# DAUGHTER_POWER.net
KiCad netlist of a schematic drawn in EAGLE
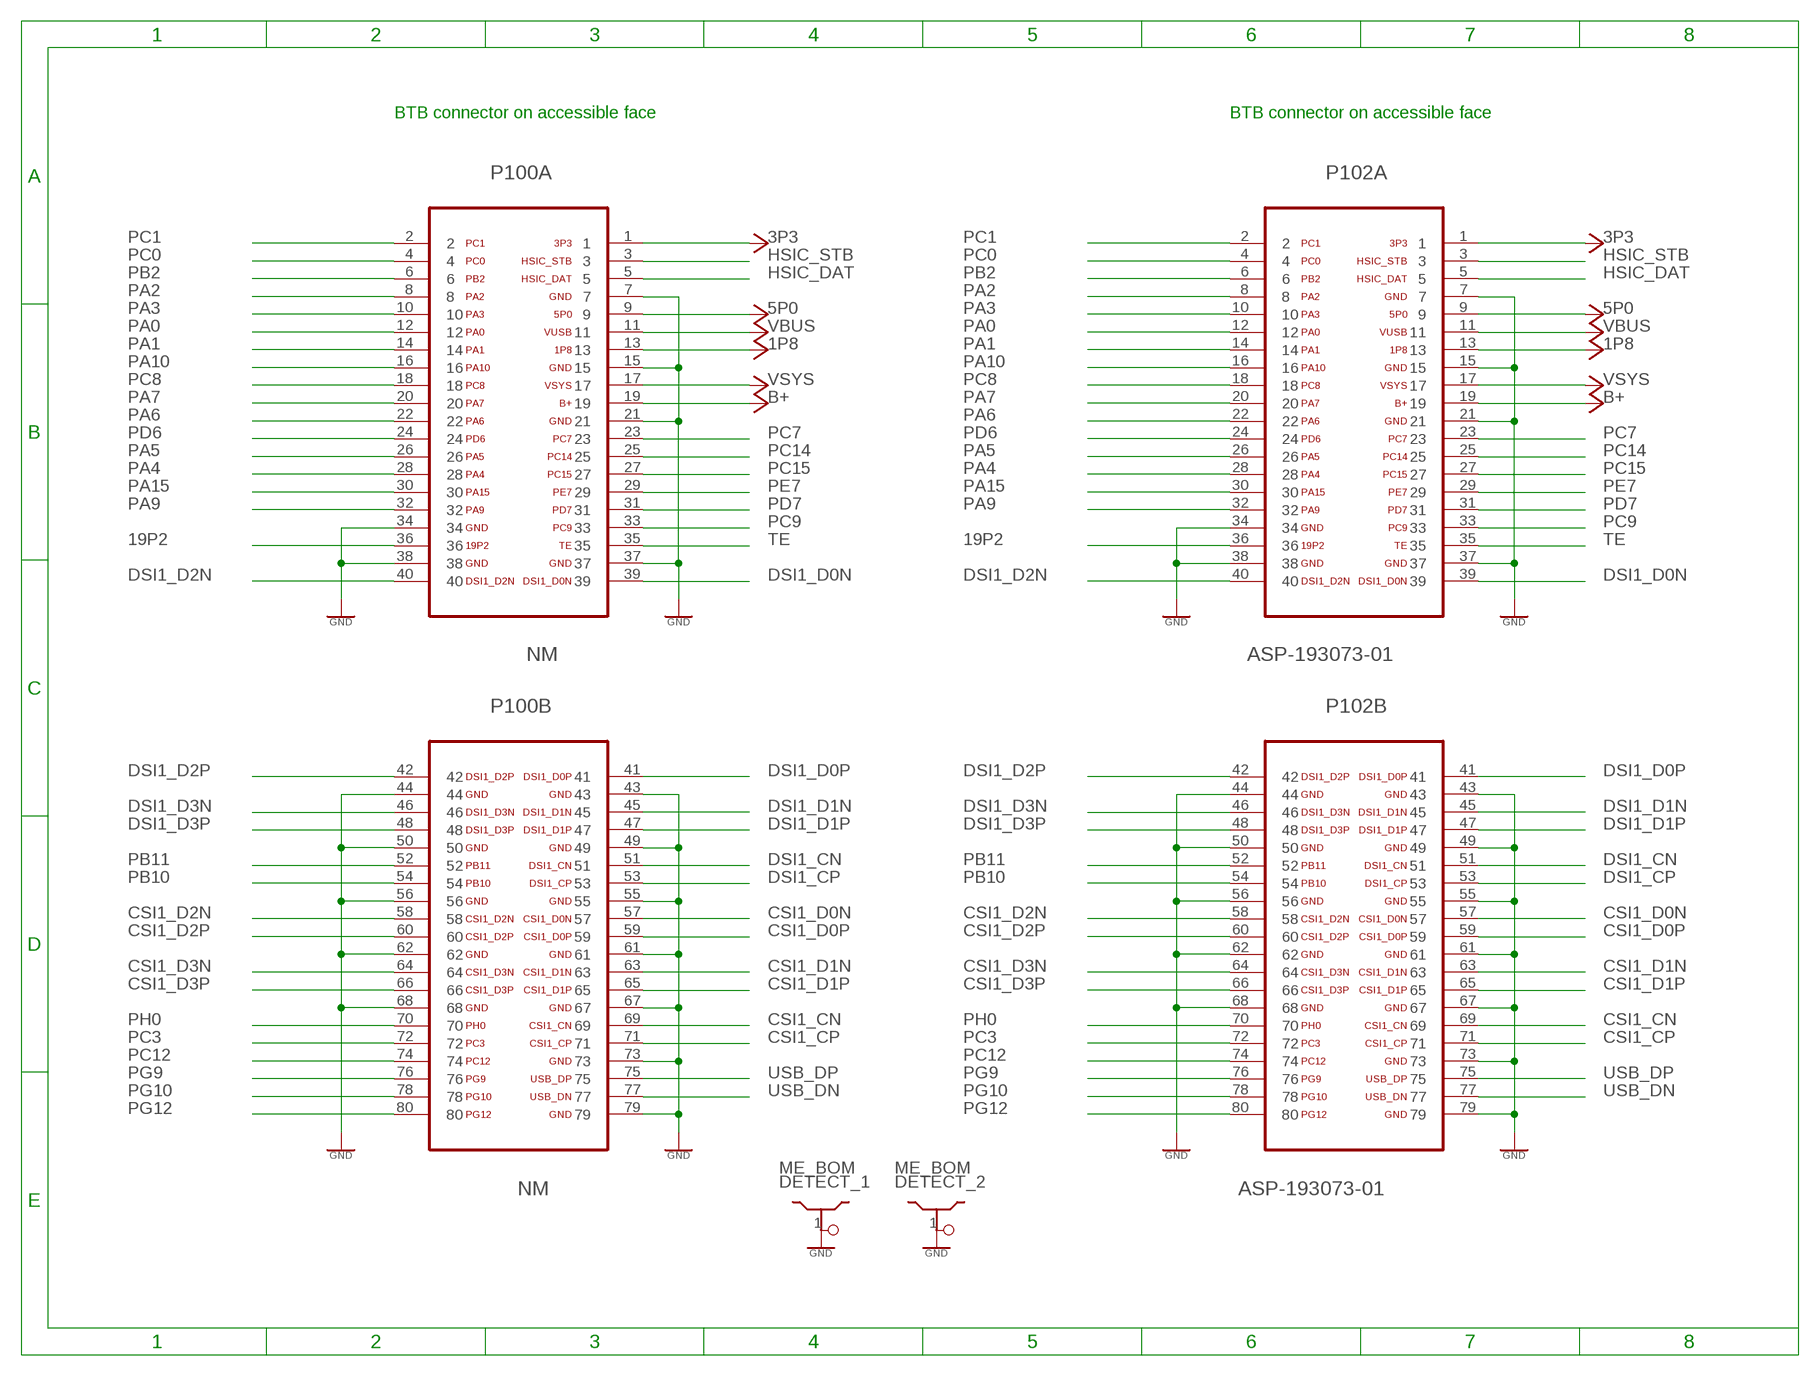
[diagram p0: schematic, sheet 1]
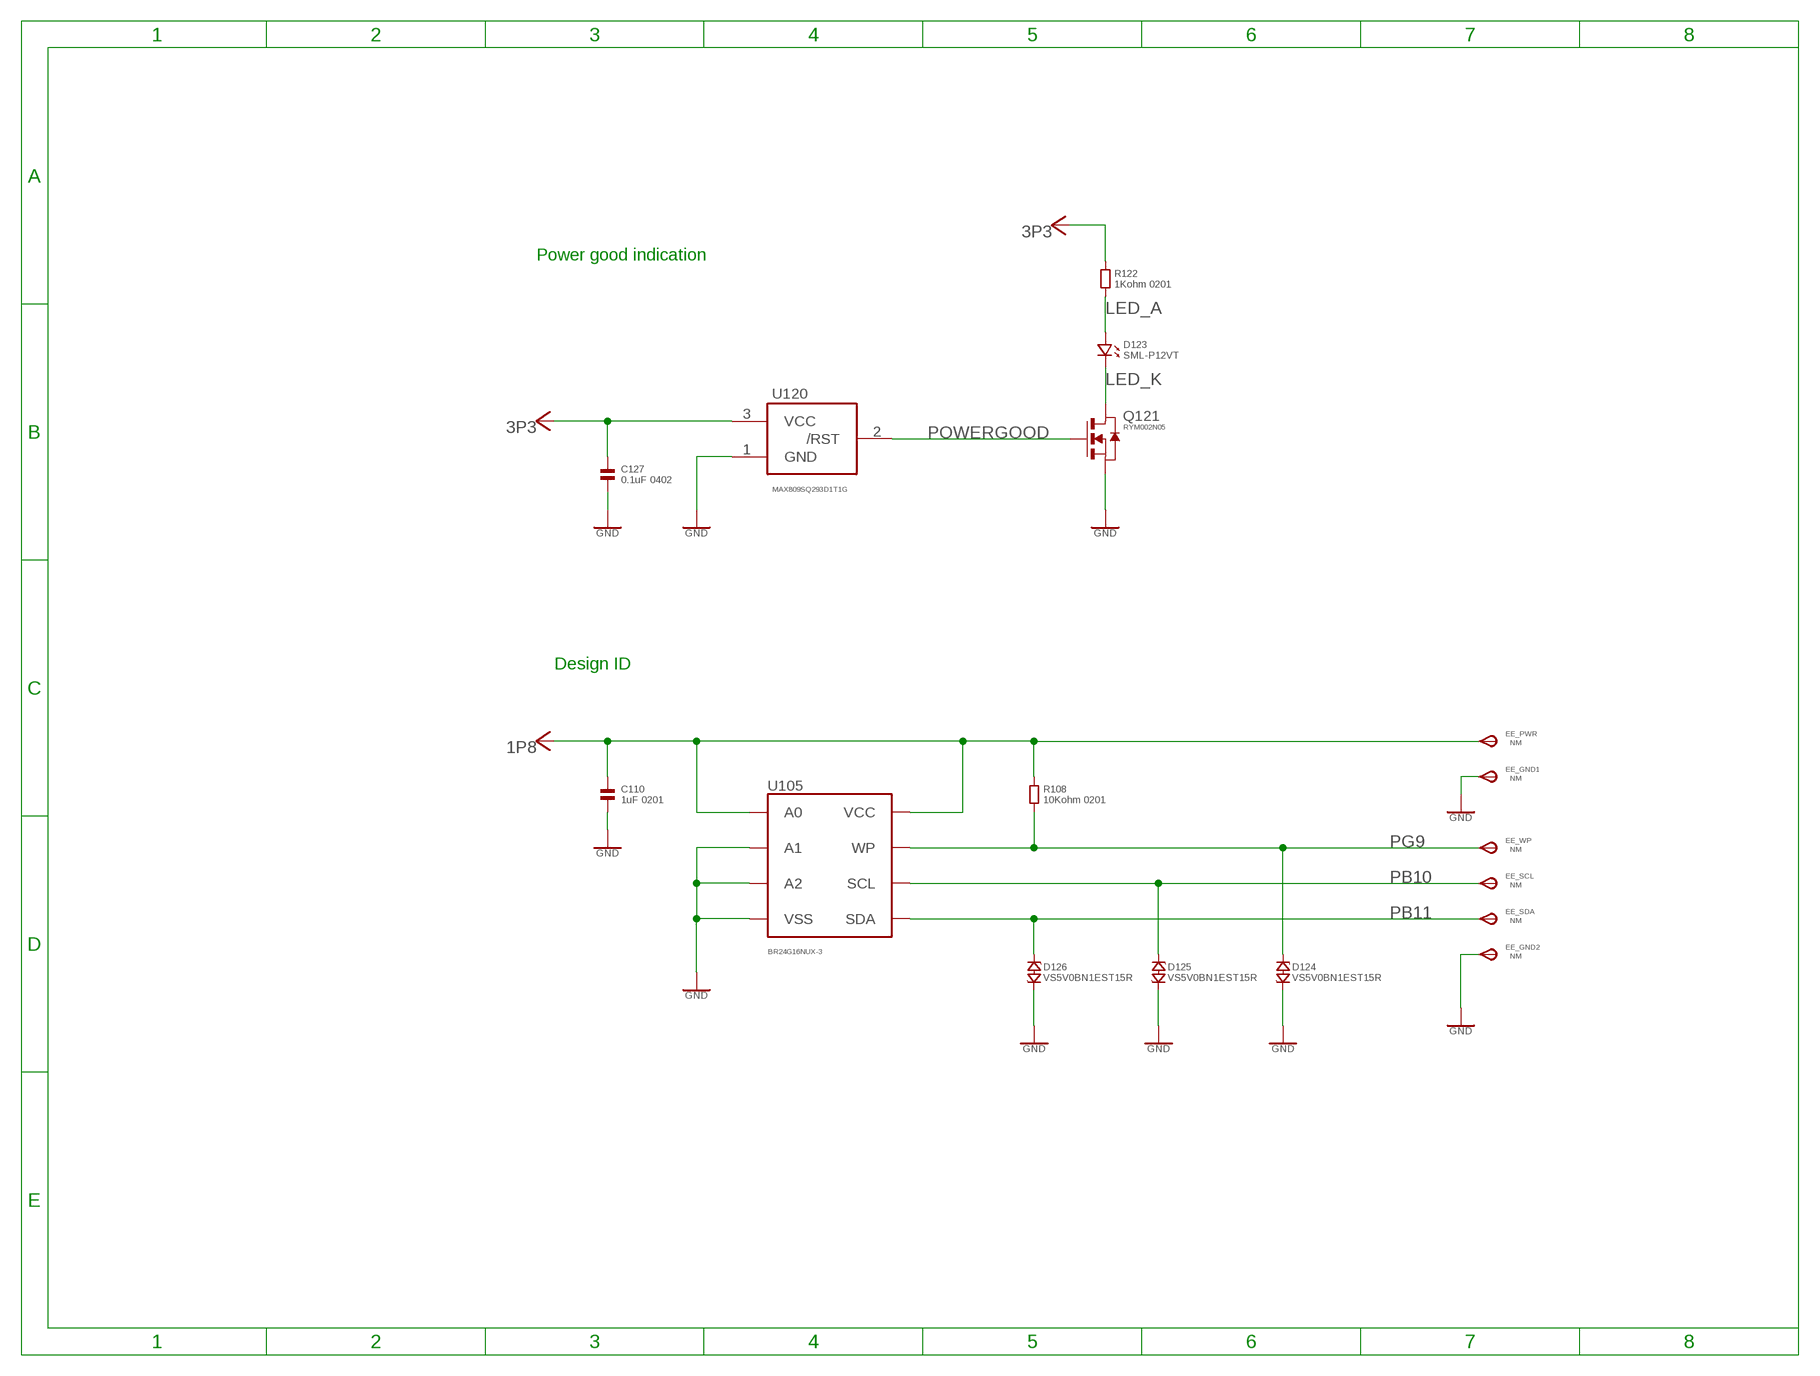
[diagram p1: schematic, sheet 2]
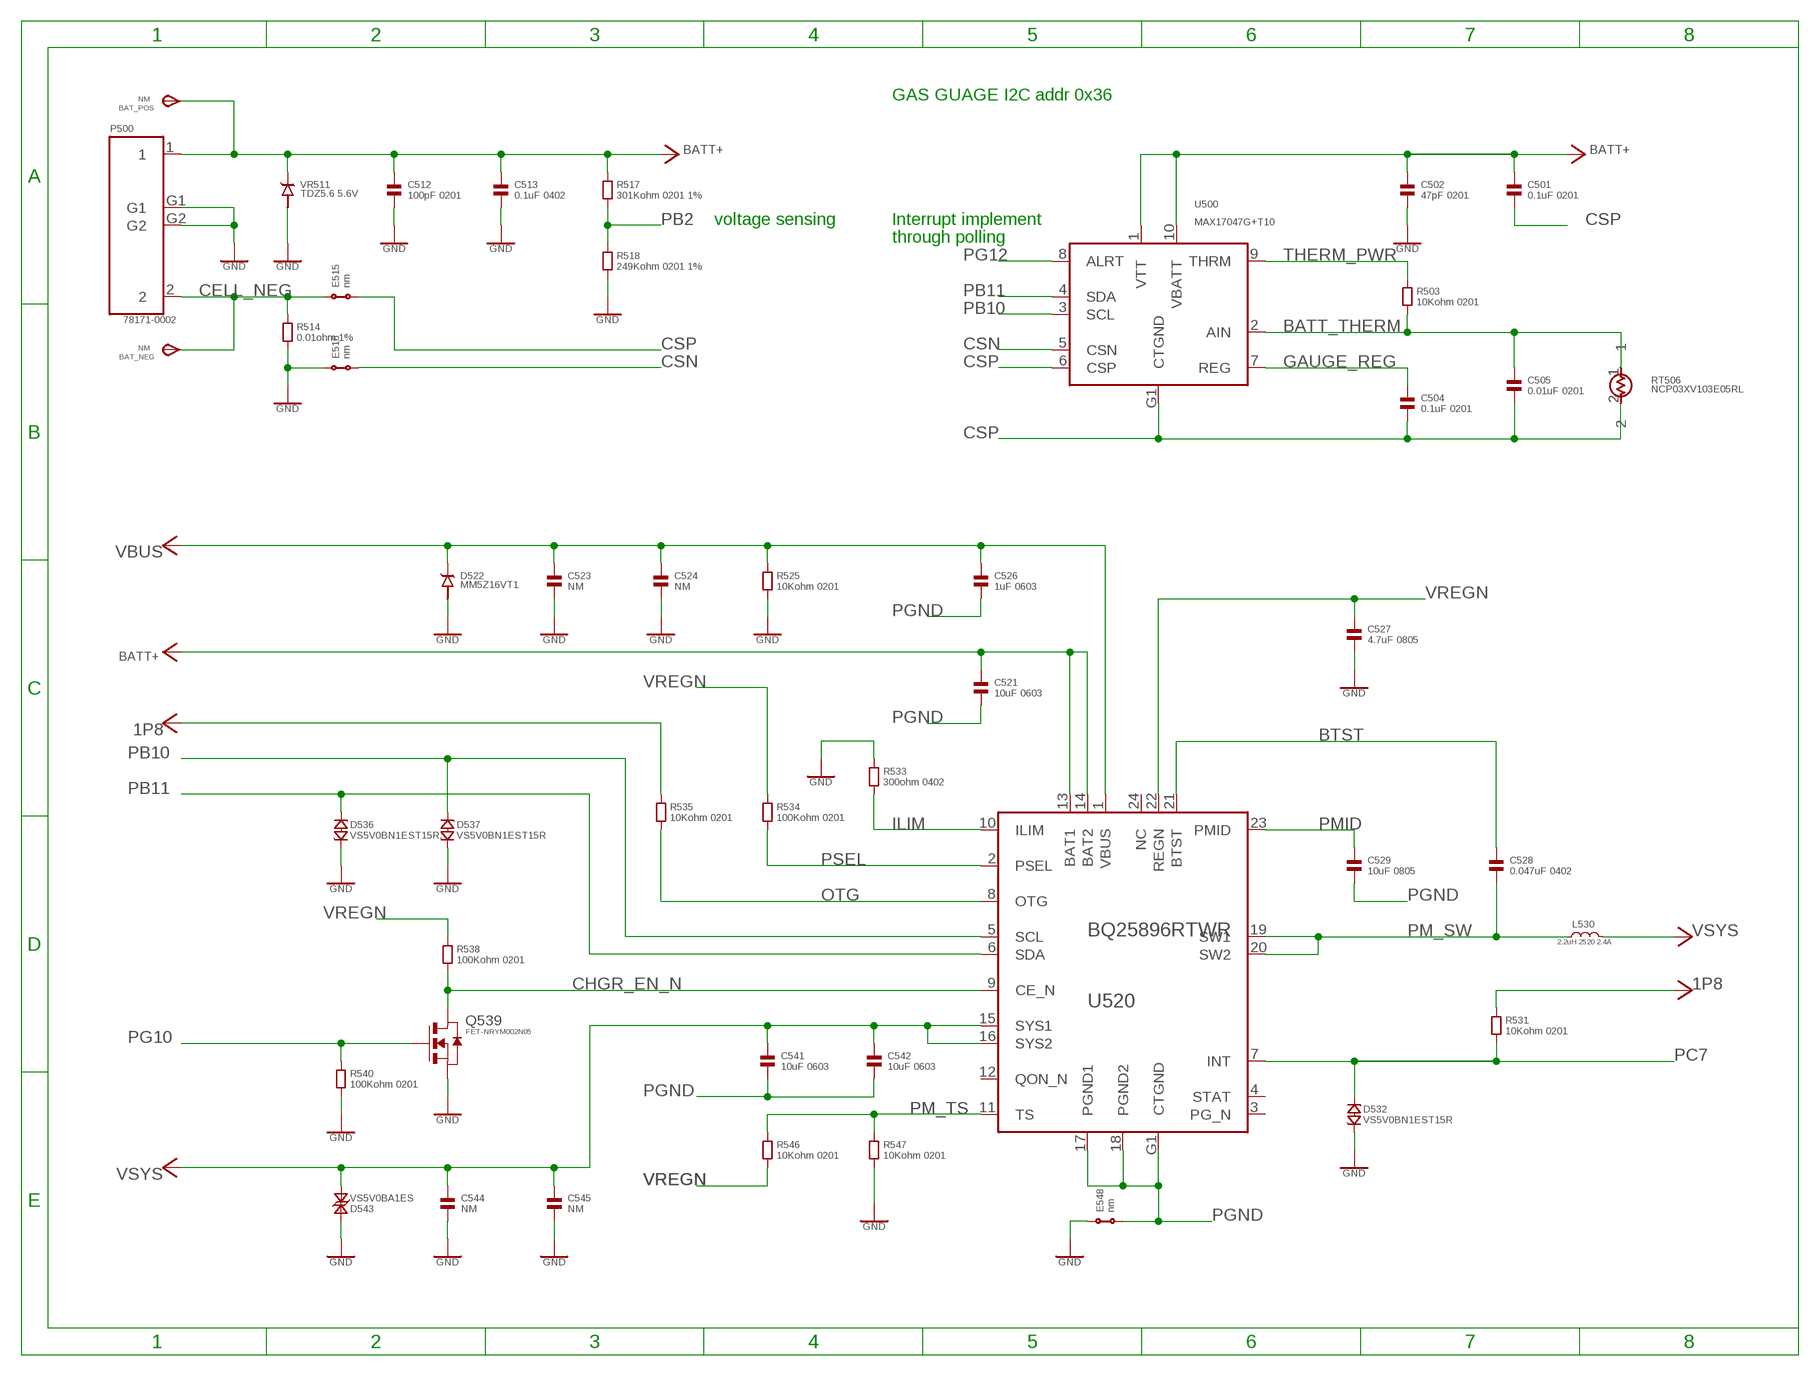
[diagram p2: schematic, sheet 3]

(export (version "E")
  (design (tool "Eeschema 10.0.6"))
  (components
    (comp (ref "BAT_NEG")
      (value "NM")
      (footprint "eagle-import:TP11R")
      (libsource (lib "eagle-import") (part "TPSTP11R"))
    )
    (comp (ref "BAT_POS")
      (value "NM")
      (footprint "eagle-import:TP11R")
      (libsource (lib "eagle-import") (part "TPSTP11R"))
    )
    (comp (ref "C501")
      (value "0.1uF 0201")
      (footprint "eagle-import:0201")
      (libsource (lib "eagle-import") (part "CAPACITOR.0201"))
    )
    (comp (ref "C502")
      (value "47pF 0201")
      (footprint "eagle-import:0201")
      (libsource (lib "eagle-import") (part "CAPACITOR.0201"))
    )
    (comp (ref "C504")
      (value "0.1uF 0201")
      (footprint "eagle-import:0201")
      (libsource (lib "eagle-import") (part "CAPACITOR.0201"))
    )
    (comp (ref "C505")
      (value "0.01uF 0201")
      (footprint "eagle-import:0201")
      (libsource (lib "eagle-import") (part "CAPACITOR.0201"))
    )
    (comp (ref "C512")
      (value "100pF 0201")
      (footprint "eagle-import:0201")
      (libsource (lib "eagle-import") (part "CAPACITOR.0201"))
    )
    (comp (ref "C513")
      (value "0.1uF 0402")
      (footprint "eagle-import:0402")
      (libsource (lib "eagle-import") (part "CAPACITOR.0402"))
    )
    (comp (ref "C521")
      (value "10uF 0603")
      (footprint "eagle-import:0603")
      (libsource (lib "eagle-import") (part "CAPACITOR.0603"))
    )
    (comp (ref "C523")
      (value "NM")
      (footprint "eagle-import:0201")
      (libsource (lib "eagle-import") (part "CAPACITOR.0201"))
    )
    (comp (ref "C524")
      (value "NM")
      (footprint "eagle-import:0201")
      (libsource (lib "eagle-import") (part "CAPACITOR.0201"))
    )
    (comp (ref "C526")
      (value "1uF 0603")
      (footprint "eagle-import:0603")
      (libsource (lib "eagle-import") (part "CAPACITOR.0603"))
    )
    (comp (ref "C527")
      (value "4.7uF 0805")
      (footprint "eagle-import:0805")
      (libsource (lib "eagle-import") (part "CAPACITOR.0805"))
    )
    (comp (ref "C528")
      (value "0.047uF 0402")
      (footprint "eagle-import:0402")
      (libsource (lib "eagle-import") (part "CAPACITOR.0402"))
    )
    (comp (ref "C529")
      (value "10uF 0805")
      (footprint "eagle-import:0805")
      (libsource (lib "eagle-import") (part "CAPACITOR.0805"))
    )
    (comp (ref "C541")
      (value "10uF 0603")
      (footprint "eagle-import:0603")
      (libsource (lib "eagle-import") (part "CAPACITOR.0603"))
    )
    (comp (ref "C542")
      (value "10uF 0603")
      (footprint "eagle-import:0603")
      (libsource (lib "eagle-import") (part "CAPACITOR.0603"))
    )
    (comp (ref "C544")
      (value "NM")
      (footprint "eagle-import:0201")
      (libsource (lib "eagle-import") (part "CAPACITOR.0201"))
    )
    (comp (ref "C545")
      (value "NM")
      (footprint "eagle-import:0201")
      (libsource (lib "eagle-import") (part "CAPACITOR.0201"))
    )
    (comp (ref "D522")
      (value "MM5Z16VT1")
      (footprint "eagle-import:SOD523")
      (libsource (lib "eagle-import") (part "DIODE.SOD523"))
    )
    (comp (ref "D532")
      (value "VS5V0BN1EST15R")
      (footprint "eagle-import:CHIP_0201")
      (libsource (lib "eagle-import") (part "ESD_VARISTOR.0201"))
    )
    (comp (ref "D536")
      (value "VS5V0BN1EST15R")
      (footprint "eagle-import:CHIP_0201")
      (libsource (lib "eagle-import") (part "ESD_VARISTOR.0201"))
    )
    (comp (ref "D537")
      (value "VS5V0BN1EST15R")
      (footprint "eagle-import:CHIP_0201")
      (libsource (lib "eagle-import") (part "ESD_VARISTOR.0201"))
    )
    (comp (ref "D543")
      (value "VS5V0BA1ES")
      (footprint "eagle-import:CHIP_0201")
      (fields (field (name "MPN") "UCLAMP1211Z"))
      (libsource (lib "eagle-import") (part "ESD_TVS.0201"))
    )
    (comp (ref "E515")
      (value "nm")
      (footprint "eagle-import:SHORT_DOT")
      (libsource (lib "eagle-import") (part "SHORT_DOT"))
    )
    (comp (ref "E516")
      (value "nm")
      (footprint "eagle-import:SHORT_DOT")
      (libsource (lib "eagle-import") (part "SHORT_DOT"))
    )
    (comp (ref "E548")
      (value "nm")
      (footprint "eagle-import:1X4_SHORT")
      (libsource (lib "eagle-import") (part "SHORT_BAR"))
    )
    (comp (ref "L530")
      (value "2.2uH 2520 2.4A")
      (footprint "eagle-import:2520")
      (libsource (lib "eagle-import") (part "POWER-INDUCTOR"))
    )
    (comp (ref "P500")
      (value "78171-0002")
      (footprint "eagle-import:CONN_4PIN")
      (libsource (lib "eagle-import") (part "CONN_BATT"))
    )
    (comp (ref "Q539")
      (value "FET-NRYM002N05")
      (footprint "eagle-import:VMT3")
      (fields (field (name "MPN") "RYM002N05"))
      (libsource (lib "eagle-import") (part "FET-NRYM002N05"))
    )
    (comp (ref "R503")
      (value "10Kohm 0201")
      (footprint "eagle-import:0201")
      (libsource (lib "eagle-import") (part "RESISTOR.0201"))
    )
    (comp (ref "R514")
      (value "0.01ohm 1%")
      (footprint "eagle-import:0805")
      (libsource (lib "eagle-import") (part "RESISTOR.0805"))
    )
    (comp (ref "R517")
      (value "301Kohm 0201 1%")
      (footprint "eagle-import:0201")
      (libsource (lib "eagle-import") (part "RESISTOR.0201"))
    )
    (comp (ref "R518")
      (value "249Kohm 0201 1%")
      (footprint "eagle-import:0201")
      (libsource (lib "eagle-import") (part "RESISTOR.0201"))
    )
    (comp (ref "R525")
      (value "10Kohm 0201")
      (footprint "eagle-import:0201")
      (libsource (lib "eagle-import") (part "RESISTOR.0201"))
    )
    (comp (ref "R531")
      (value "10Kohm 0201")
      (footprint "eagle-import:0201")
      (libsource (lib "eagle-import") (part "RESISTOR.0201"))
    )
    (comp (ref "R533")
      (value "300ohm 0402")
      (footprint "eagle-import:0402")
      (libsource (lib "eagle-import") (part "RESISTOR.0402"))
    )
    (comp (ref "R534")
      (value "100Kohm 0201")
      (footprint "eagle-import:0201")
      (libsource (lib "eagle-import") (part "RESISTOR.0201"))
    )
    (comp (ref "R535")
      (value "10Kohm 0201")
      (footprint "eagle-import:0201")
      (libsource (lib "eagle-import") (part "RESISTOR.0201"))
    )
    (comp (ref "R538")
      (value "100Kohm 0201")
      (footprint "eagle-import:0201")
      (libsource (lib "eagle-import") (part "RESISTOR.0201"))
    )
    (comp (ref "R540")
      (value "100Kohm 0201")
      (footprint "eagle-import:0201")
      (libsource (lib "eagle-import") (part "RESISTOR.0201"))
    )
    (comp (ref "R546")
      (value "10Kohm 0201")
      (footprint "eagle-import:0201")
      (libsource (lib "eagle-import") (part "RESISTOR.0201"))
    )
    (comp (ref "R547")
      (value "10Kohm 0201")
      (footprint "eagle-import:0201")
      (libsource (lib "eagle-import") (part "RESISTOR.0201"))
    )
    (comp (ref "RT506")
      (value "NCP03XV103E05RL")
      (footprint "eagle-import:0201")
      (fields (field (name "MPN") "NCP03XV103XV103E05RL/NTCG0603UH103HT"))
      (libsource (lib "eagle-import") (part "THERMISTOR"))
    )
    (comp (ref "U500")
      (value "MAX17047G+T10")
      (footprint "eagle-import:DFN3X3_PS0_5P11")
      (libsource (lib "eagle-import") (part "MAX17047G+T10"))
    )
    (comp (ref "U520")
      (value "BQ25896RTWR")
      (footprint "eagle-import:QFN4X4PS0_5P25")
      (libsource (lib "eagle-import") (part "BQ25896RTWR"))
    )
    (comp (ref "VR511")
      (value "TDZ5.6 5.6V")
      (footprint "eagle-import:DIO1_9X1_3")
      (fields (field (name "MPN") "TDZ5.6B"))
      (libsource (lib "eagle-import") (part "DIODE"))
    )
    (comp (ref "C110")
      (value "1uF 0201")
      (footprint "eagle-import:0201")
      (libsource (lib "eagle-import") (part "CAPACITOR.0201"))
    )
    (comp (ref "C127")
      (value "0.1uF 0402")
      (footprint "eagle-import:0402")
      (libsource (lib "eagle-import") (part "CAPACITOR.0402"))
    )
    (comp (ref "D123")
      (value "SML-P12VT")
      (footprint "eagle-import:0503.LED")
      (libsource (lib "eagle-import") (part "LED.0503"))
    )
    (comp (ref "D124")
      (value "VS5V0BN1EST15R")
      (footprint "eagle-import:CHIP_0201")
      (libsource (lib "eagle-import") (part "ESD_VARISTOR.0201"))
    )
    (comp (ref "D125")
      (value "VS5V0BN1EST15R")
      (footprint "eagle-import:CHIP_0201")
      (libsource (lib "eagle-import") (part "ESD_VARISTOR.0201"))
    )
    (comp (ref "D126")
      (value "VS5V0BN1EST15R")
      (footprint "eagle-import:CHIP_0201")
      (libsource (lib "eagle-import") (part "ESD_VARISTOR.0201"))
    )
    (comp (ref "EE_GND1")
      (value "NM")
      (footprint "eagle-import:TP11R")
      (libsource (lib "eagle-import") (part "TPSTP11R"))
    )
    (comp (ref "EE_GND2")
      (value "NM")
      (footprint "eagle-import:TP11R")
      (libsource (lib "eagle-import") (part "TPSTP11R"))
    )
    (comp (ref "EE_PWR")
      (value "NM")
      (footprint "eagle-import:TP11R")
      (libsource (lib "eagle-import") (part "TPSTP11R"))
    )
    (comp (ref "EE_SCL")
      (value "NM")
      (footprint "eagle-import:TP11R")
      (libsource (lib "eagle-import") (part "TPSTP11R"))
    )
    (comp (ref "EE_SDA")
      (value "NM")
      (footprint "eagle-import:TP11R")
      (libsource (lib "eagle-import") (part "TPSTP11R"))
    )
    (comp (ref "EE_WP")
      (value "NM")
      (footprint "eagle-import:TP11R")
      (libsource (lib "eagle-import") (part "TPSTP11R"))
    )
    (comp (ref "Q121")
      (value "RYM002N05")
      (footprint "eagle-import:VMT3")
      (libsource (lib "eagle-import") (part "FET-NRYM002N05"))
    )
    (comp (ref "R108")
      (value "10Kohm 0201")
      (footprint "eagle-import:0201")
      (libsource (lib "eagle-import") (part "RESISTOR.0201"))
    )
    (comp (ref "R122")
      (value "1Kohm 0201")
      (footprint "eagle-import:0201")
      (libsource (lib "eagle-import") (part "RESISTOR.0201"))
    )
    (comp (ref "U105")
      (value "BR24G16NUX-3")
      (footprint "eagle-import:DFN-8")
      (libsource (lib "eagle-import") (part "EEPROMDFN8"))
    )
    (comp (ref "U120")
      (value "MAX809SQ293D1T1G")
      (footprint "eagle-import:SC70-3L")
      (fields (field (name "MPN") "MAX809SQ293D1T1"))
      (libsource (lib "eagle-import") (part "MAX809"))
    )
    (comp (ref "DETECT_1")
      (value "ME_BOM")
      (footprint "eagle-import:PLUG")
      (fields (field (name "MPN") "refer to ME BOM"))
      (libsource (lib "eagle-import") (part "SHIELDDETECT"))
    )
    (comp (ref "DETECT_2")
      (value "ME_BOM")
      (footprint "eagle-import:PLUG")
      (fields (field (name "MPN") "refer to ME BOM"))
      (libsource (lib "eagle-import") (part "SHIELDDETECT"))
    )
    (comp (ref "P100")
      (value "NM")
      (footprint "eagle-import:CLM-140-02-L-D-K_GOLD")
      (fields (field (name "MPN") "CLM-140-02-L-D-K"))
      (libsource (lib "eagle-import") (part "CLM-140-02-L-D-KGOLD"))
    )
    (comp (ref "P102")
      (value "ASP-193073-01")
      (footprint "eagle-import:FTMH-140-02-L-DV-ES-P-TR")
      (fields (field (name "MPN") "ASP-193073-01"))
      (libsource (lib "eagle-import") (part "FTMH-140-02-L-DV-ES-P-TR"))
    )
  )
  (nets
    (net (code "1") (name "1P8") (class "Default")
      (node (ref "C110") (pin "1") (pinfunction "1_1") (pintype "bidirectional"))
      (node (ref "EE_PWR") (pin "TP") (pinfunction "PP_TP") (pintype "input"))
      (node (ref "P100") (pin "13") (pinfunction "13_13") (pintype "passive"))
      (node (ref "P102") (pin "13") (pinfunction "13_13") (pintype "passive"))
      (node (ref "R108") (pin "1") (pinfunction "1_1") (pintype "bidirectional"))
      (node (ref "R531") (pin "1") (pinfunction "1_1") (pintype "bidirectional"))
      (node (ref "R535") (pin "1") (pinfunction "1_1") (pintype "bidirectional"))
      (node (ref "U105") (pin "P$1") (pinfunction "A0_P$1") (pintype "input"))
      (node (ref "U105") (pin "P$8") (pinfunction "VCC_P$8") (pintype "power_in"))
    )
    (net (code "2") (name "3P3") (class "Default")
      (node (ref "C127") (pin "1") (pinfunction "1_1") (pintype "bidirectional"))
      (node (ref "P100") (pin "1") (pinfunction "1_1") (pintype "passive"))
      (node (ref "P102") (pin "1") (pinfunction "1_1") (pintype "passive"))
      (node (ref "R122") (pin "1") (pinfunction "1_1") (pintype "bidirectional"))
      (node (ref "U120") (pin "3") (pinfunction "VCC_3") (pintype "input"))
    )
    (net (code "3") (name "5P0") (class "Default")
      (node (ref "P100") (pin "9") (pinfunction "9_9") (pintype "passive"))
      (node (ref "P102") (pin "9") (pinfunction "9_9") (pintype "passive"))
    )
    (net (code "4") (name "19P2") (class "Default")
      (node (ref "P100") (pin "36") (pinfunction "36_36") (pintype "passive"))
      (node (ref "P102") (pin "36") (pinfunction "36_36") (pintype "passive"))
    )
    (net (code "5") (name "B+") (class "Default")
      (node (ref "P100") (pin "19") (pinfunction "19_19") (pintype "passive"))
      (node (ref "P102") (pin "19") (pinfunction "19_19") (pintype "passive"))
    )
    (net (code "6") (name "BATT+") (class "Default")
      (node (ref "BAT_POS") (pin "TP") (pinfunction "PP_TP") (pintype "input"))
      (node (ref "C501") (pin "1") (pinfunction "1_1") (pintype "bidirectional"))
      (node (ref "C502") (pin "1") (pinfunction "1_1") (pintype "bidirectional"))
      (node (ref "C512") (pin "1") (pinfunction "1_1") (pintype "bidirectional"))
      (node (ref "C513") (pin "1") (pinfunction "1_1") (pintype "bidirectional"))
      (node (ref "C521") (pin "1") (pinfunction "1_1") (pintype "bidirectional"))
      (node (ref "P500") (pin "1") (pinfunction "1_1") (pintype "bidirectional"))
      (node (ref "R517") (pin "1") (pinfunction "1_1") (pintype "bidirectional"))
      (node (ref "U500") (pin "1") (pinfunction "VTT_1") (pintype "bidirectional"))
      (node (ref "U500") (pin "10") (pinfunction "VBATT_10") (pintype "bidirectional"))
      (node (ref "U520") (pin "13") (pinfunction "BAT1_13") (pintype "bidirectional"))
      (node (ref "U520") (pin "14") (pinfunction "BAT2_14") (pintype "bidirectional"))
      (node (ref "VR511") (pin "1") (pinfunction "1_1") (pintype "bidirectional"))
    )
    (net (code "7") (name "BATT_THERM") (class "Default")
      (node (ref "C505") (pin "1") (pinfunction "1_1") (pintype "bidirectional"))
      (node (ref "R503") (pin "2") (pinfunction "2_2") (pintype "bidirectional"))
      (node (ref "RT506") (pin "1") (pinfunction "1_1") (pintype "bidirectional"))
      (node (ref "U500") (pin "2") (pinfunction "AIN_2") (pintype "bidirectional"))
    )
    (net (code "8") (name "BTST") (class "Default")
      (node (ref "C528") (pin "1") (pinfunction "1_1") (pintype "bidirectional"))
      (node (ref "U520") (pin "21") (pinfunction "BTST_21") (pintype "bidirectional"))
    )
    (net (code "9") (name "CELL_NEG") (class "Default")
      (node (ref "BAT_NEG") (pin "TP") (pinfunction "PP_TP") (pintype "input"))
      (node (ref "E515") (pin "1") (pinfunction "1_1") (pintype "bidirectional"))
      (node (ref "P500") (pin "2") (pinfunction "2_2") (pintype "bidirectional"))
      (node (ref "R514") (pin "1") (pinfunction "1_1") (pintype "bidirectional"))
    )
    (net (code "10") (name "CHGR_EN_N") (class "Default")
      (node (ref "Q539") (pin "3") (pinfunction "D_3") (pintype "passive"))
      (node (ref "R538") (pin "2") (pinfunction "2_2") (pintype "bidirectional"))
      (node (ref "U520") (pin "9") (pinfunction "CE_N_9") (pintype "bidirectional"))
    )
    (net (code "11") (name "CSI1_CN") (class "Default")
      (node (ref "P100") (pin "69") (pinfunction "69_69") (pintype "passive"))
      (node (ref "P102") (pin "69") (pinfunction "69_69") (pintype "passive"))
    )
    (net (code "12") (name "CSI1_CP") (class "Default")
      (node (ref "P100") (pin "71") (pinfunction "71_71") (pintype "passive"))
      (node (ref "P102") (pin "71") (pinfunction "71_71") (pintype "passive"))
    )
    (net (code "13") (name "CSI1_D0N") (class "Default")
      (node (ref "P100") (pin "57") (pinfunction "57_57") (pintype "passive"))
      (node (ref "P102") (pin "57") (pinfunction "57_57") (pintype "passive"))
    )
    (net (code "14") (name "CSI1_D0P") (class "Default")
      (node (ref "P100") (pin "59") (pinfunction "59_59") (pintype "passive"))
      (node (ref "P102") (pin "59") (pinfunction "59_59") (pintype "passive"))
    )
    (net (code "15") (name "CSI1_D1N") (class "Default")
      (node (ref "P100") (pin "63") (pinfunction "63_63") (pintype "passive"))
      (node (ref "P102") (pin "63") (pinfunction "63_63") (pintype "passive"))
    )
    (net (code "16") (name "CSI1_D1P") (class "Default")
      (node (ref "P100") (pin "65") (pinfunction "65_65") (pintype "passive"))
      (node (ref "P102") (pin "65") (pinfunction "65_65") (pintype "passive"))
    )
    (net (code "17") (name "CSI1_D2N") (class "Default")
      (node (ref "P100") (pin "58") (pinfunction "58_58") (pintype "passive"))
      (node (ref "P102") (pin "58") (pinfunction "58_58") (pintype "passive"))
    )
    (net (code "18") (name "CSI1_D2P") (class "Default")
      (node (ref "P100") (pin "60") (pinfunction "60_60") (pintype "passive"))
      (node (ref "P102") (pin "60") (pinfunction "60_60") (pintype "passive"))
    )
    (net (code "19") (name "CSI1_D3N") (class "Default")
      (node (ref "P100") (pin "64") (pinfunction "64_64") (pintype "passive"))
      (node (ref "P102") (pin "64") (pinfunction "64_64") (pintype "passive"))
    )
    (net (code "20") (name "CSI1_D3P") (class "Default")
      (node (ref "P100") (pin "66") (pinfunction "66_66") (pintype "passive"))
      (node (ref "P102") (pin "66") (pinfunction "66_66") (pintype "passive"))
    )
    (net (code "21") (name "CSN") (class "Default")
      (node (ref "E516") (pin "2") (pinfunction "2_2") (pintype "bidirectional"))
      (node (ref "U500") (pin "5") (pinfunction "CSN_5") (pintype "bidirectional"))
    )
    (net (code "22") (name "CSP") (class "Default")
      (node (ref "C501") (pin "2") (pinfunction "2_2") (pintype "bidirectional"))
      (node (ref "C504") (pin "2") (pinfunction "2_2") (pintype "bidirectional"))
      (node (ref "C505") (pin "2") (pinfunction "2_2") (pintype "bidirectional"))
      (node (ref "E515") (pin "2") (pinfunction "2_2") (pintype "bidirectional"))
      (node (ref "RT506") (pin "2") (pinfunction "2_2") (pintype "bidirectional"))
      (node (ref "U500") (pin "6") (pinfunction "CSP_6") (pintype "bidirectional"))
      (node (ref "U500") (pin "G1") (pinfunction "CTGND_G1") (pintype "bidirectional"))
    )
    (net (code "23") (name "DSI1_CN") (class "Default")
      (node (ref "P100") (pin "51") (pinfunction "51_51") (pintype "passive"))
      (node (ref "P102") (pin "51") (pinfunction "51_51") (pintype "passive"))
    )
    (net (code "24") (name "DSI1_CP") (class "Default")
      (node (ref "P100") (pin "53") (pinfunction "53_53") (pintype "passive"))
      (node (ref "P102") (pin "53") (pinfunction "53_53") (pintype "passive"))
    )
    (net (code "25") (name "DSI1_D0N") (class "Default")
      (node (ref "P100") (pin "39") (pinfunction "39_39") (pintype "passive"))
      (node (ref "P102") (pin "39") (pinfunction "39_39") (pintype "passive"))
    )
    (net (code "26") (name "DSI1_D0P") (class "Default")
      (node (ref "P100") (pin "41") (pinfunction "41_41") (pintype "passive"))
      (node (ref "P102") (pin "41") (pinfunction "41_41") (pintype "passive"))
    )
    (net (code "27") (name "DSI1_D1N") (class "Default")
      (node (ref "P100") (pin "45") (pinfunction "45_45") (pintype "passive"))
      (node (ref "P102") (pin "45") (pinfunction "45_45") (pintype "passive"))
    )
    (net (code "28") (name "DSI1_D1P") (class "Default")
      (node (ref "P100") (pin "47") (pinfunction "47_47") (pintype "passive"))
      (node (ref "P102") (pin "47") (pinfunction "47_47") (pintype "passive"))
    )
    (net (code "29") (name "DSI1_D2N") (class "Default")
      (node (ref "P100") (pin "40") (pinfunction "40_40") (pintype "passive"))
      (node (ref "P102") (pin "40") (pinfunction "40_40") (pintype "passive"))
    )
    (net (code "30") (name "DSI1_D2P") (class "Default")
      (node (ref "P100") (pin "42") (pinfunction "42_42") (pintype "passive"))
      (node (ref "P102") (pin "42") (pinfunction "42_42") (pintype "passive"))
    )
    (net (code "31") (name "DSI1_D3N") (class "Default")
      (node (ref "P100") (pin "46") (pinfunction "46_46") (pintype "passive"))
      (node (ref "P102") (pin "46") (pinfunction "46_46") (pintype "passive"))
    )
    (net (code "32") (name "DSI1_D3P") (class "Default")
      (node (ref "P100") (pin "48") (pinfunction "48_48") (pintype "passive"))
      (node (ref "P102") (pin "48") (pinfunction "48_48") (pintype "passive"))
    )
    (net (code "33") (name "GAUGE_REG") (class "Default")
      (node (ref "C504") (pin "1") (pinfunction "1_1") (pintype "bidirectional"))
      (node (ref "U500") (pin "7") (pinfunction "REG_7") (pintype "bidirectional"))
    )
    (net (code "34") (name "GND") (class "Default")
      (node (ref "C110") (pin "2") (pinfunction "2_2") (pintype "bidirectional"))
      (node (ref "C127") (pin "2") (pinfunction "2_2") (pintype "bidirectional"))
      (node (ref "C502") (pin "2") (pinfunction "2_2") (pintype "bidirectional"))
      (node (ref "C512") (pin "2") (pinfunction "2_2") (pintype "bidirectional"))
      (node (ref "C513") (pin "2") (pinfunction "2_2") (pintype "bidirectional"))
      (node (ref "C523") (pin "2") (pinfunction "2_2") (pintype "bidirectional"))
      (node (ref "C524") (pin "2") (pinfunction "2_2") (pintype "bidirectional"))
      (node (ref "C527") (pin "2") (pinfunction "2_2") (pintype "bidirectional"))
      (node (ref "C544") (pin "2") (pinfunction "2_2") (pintype "bidirectional"))
      (node (ref "C545") (pin "2") (pinfunction "2_2") (pintype "bidirectional"))
      (node (ref "D124") (pin "P$2") (pinfunction "2_P$2") (pintype "bidirectional"))
      (node (ref "D125") (pin "P$2") (pinfunction "2_P$2") (pintype "bidirectional"))
      (node (ref "D126") (pin "P$2") (pinfunction "2_P$2") (pintype "bidirectional"))
      (node (ref "D522") (pin "2") (pinfunction "2_2") (pintype "bidirectional"))
      (node (ref "D532") (pin "P$2") (pinfunction "2_P$2") (pintype "bidirectional"))
      (node (ref "D536") (pin "P$2") (pinfunction "2_P$2") (pintype "bidirectional"))
      (node (ref "D537") (pin "P$2") (pinfunction "2_P$2") (pintype "bidirectional"))
      (node (ref "D543") (pin "P$1") (pinfunction "1_P$1") (pintype "bidirectional"))
      (node (ref "DETECT_1") (pin "1") (pinfunction "1_1") (pintype "passive"))
      (node (ref "DETECT_2") (pin "1") (pinfunction "1_1") (pintype "passive"))
      (node (ref "E516") (pin "1") (pinfunction "1_1") (pintype "bidirectional"))
      (node (ref "E548") (pin "1") (pinfunction "1_1") (pintype "bidirectional"))
      (node (ref "EE_GND1") (pin "TP") (pinfunction "PP_TP") (pintype "input"))
      (node (ref "EE_GND2") (pin "TP") (pinfunction "PP_TP") (pintype "input"))
      (node (ref "P100") (pin "15") (pinfunction "15_15") (pintype "passive"))
      (node (ref "P100") (pin "21") (pinfunction "21_21") (pintype "passive"))
      (node (ref "P100") (pin "34") (pinfunction "34_34") (pintype "passive"))
      (node (ref "P100") (pin "37") (pinfunction "37_37") (pintype "passive"))
      (node (ref "P100") (pin "38") (pinfunction "38_38") (pintype "passive"))
      (node (ref "P100") (pin "43") (pinfunction "43_43") (pintype "passive"))
      (node (ref "P100") (pin "44") (pinfunction "44_44") (pintype "passive"))
      (node (ref "P100") (pin "49") (pinfunction "49_49") (pintype "passive"))
      (node (ref "P100") (pin "50") (pinfunction "50_50") (pintype "passive"))
      (node (ref "P100") (pin "55") (pinfunction "55_55") (pintype "passive"))
      (node (ref "P100") (pin "56") (pinfunction "56_56") (pintype "passive"))
      (node (ref "P100") (pin "61") (pinfunction "61_61") (pintype "passive"))
      (node (ref "P100") (pin "62") (pinfunction "62_62") (pintype "passive"))
      (node (ref "P100") (pin "67") (pinfunction "67_67") (pintype "passive"))
      (node (ref "P100") (pin "68") (pinfunction "68_68") (pintype "passive"))
      (node (ref "P100") (pin "7") (pinfunction "7_7") (pintype "passive"))
      (node (ref "P100") (pin "73") (pinfunction "73_73") (pintype "passive"))
      (node (ref "P100") (pin "79") (pinfunction "79_79") (pintype "passive"))
      (node (ref "P102") (pin "15") (pinfunction "15_15") (pintype "passive"))
      (node (ref "P102") (pin "21") (pinfunction "21_21") (pintype "passive"))
      (node (ref "P102") (pin "34") (pinfunction "34_34") (pintype "passive"))
      (node (ref "P102") (pin "37") (pinfunction "37_37") (pintype "passive"))
      (node (ref "P102") (pin "38") (pinfunction "38_38") (pintype "passive"))
      (node (ref "P102") (pin "43") (pinfunction "43_43") (pintype "passive"))
      (node (ref "P102") (pin "44") (pinfunction "44_44") (pintype "passive"))
      (node (ref "P102") (pin "49") (pinfunction "49_49") (pintype "passive"))
      (node (ref "P102") (pin "50") (pinfunction "50_50") (pintype "passive"))
      (node (ref "P102") (pin "55") (pinfunction "55_55") (pintype "passive"))
      (node (ref "P102") (pin "56") (pinfunction "56_56") (pintype "passive"))
      (node (ref "P102") (pin "61") (pinfunction "61_61") (pintype "passive"))
      (node (ref "P102") (pin "62") (pinfunction "62_62") (pintype "passive"))
      (node (ref "P102") (pin "67") (pinfunction "67_67") (pintype "passive"))
      (node (ref "P102") (pin "68") (pinfunction "68_68") (pintype "passive"))
      (node (ref "P102") (pin "7") (pinfunction "7_7") (pintype "passive"))
      (node (ref "P102") (pin "73") (pinfunction "73_73") (pintype "passive"))
      (node (ref "P102") (pin "79") (pinfunction "79_79") (pintype "passive"))
      (node (ref "P500") (pin "G1") (pinfunction "G1_G1") (pintype "bidirectional"))
      (node (ref "P500") (pin "G2") (pinfunction "G2_G2") (pintype "bidirectional"))
      (node (ref "Q121") (pin "2") (pinfunction "S_2") (pintype "passive"))
      (node (ref "Q539") (pin "2") (pinfunction "S_2") (pintype "passive"))
      (node (ref "R514") (pin "2") (pinfunction "2_2") (pintype "bidirectional"))
      (node (ref "R518") (pin "2") (pinfunction "2_2") (pintype "bidirectional"))
      (node (ref "R525") (pin "2") (pinfunction "2_2") (pintype "bidirectional"))
      (node (ref "R533") (pin "1") (pinfunction "1_1") (pintype "bidirectional"))
      (node (ref "R540") (pin "2") (pinfunction "2_2") (pintype "bidirectional"))
      (node (ref "R547") (pin "2") (pinfunction "2_2") (pintype "bidirectional"))
      (node (ref "U105") (pin "P$2") (pinfunction "A1_P$2") (pintype "input"))
      (node (ref "U105") (pin "P$3") (pinfunction "A2_P$3") (pintype "input"))
      (node (ref "U105") (pin "P$4") (pinfunction "VSS_P$4") (pintype "power_in"))
      (node (ref "U105") (pin "P$9") (pinfunction "VSS_P$9") (pintype "power_in"))
      (node (ref "U120") (pin "1") (pinfunction "GND_1") (pintype "power_in"))
      (node (ref "VR511") (pin "2") (pinfunction "2_2") (pintype "bidirectional"))
    )
    (net (code "35") (name "HSIC_DAT") (class "Default")
      (node (ref "P100") (pin "5") (pinfunction "5_5") (pintype "passive"))
      (node (ref "P102") (pin "5") (pinfunction "5_5") (pintype "passive"))
    )
    (net (code "36") (name "HSIC_STB") (class "Default")
      (node (ref "P100") (pin "3") (pinfunction "3_3") (pintype "passive"))
      (node (ref "P102") (pin "3") (pinfunction "3_3") (pintype "passive"))
    )
    (net (code "37") (name "ILIM") (class "Default")
      (node (ref "R533") (pin "2") (pinfunction "2_2") (pintype "bidirectional"))
      (node (ref "U520") (pin "10") (pinfunction "ILIM_10") (pintype "bidirectional"))
    )
    (net (code "38") (name "LED_A") (class "Default")
      (node (ref "D123") (pin "P$1") (pinfunction "1_P$1") (pintype "bidirectional"))
      (node (ref "R122") (pin "2") (pinfunction "2_2") (pintype "bidirectional"))
    )
    (net (code "39") (name "LED_K") (class "Default")
      (node (ref "D123") (pin "P$2") (pinfunction "2_P$2") (pintype "bidirectional"))
      (node (ref "Q121") (pin "3") (pinfunction "D_3") (pintype "passive"))
    )
    (net (code "40") (name "OTG") (class "Default")
      (node (ref "R535") (pin "2") (pinfunction "2_2") (pintype "bidirectional"))
      (node (ref "U520") (pin "8") (pinfunction "OTG_8") (pintype "bidirectional"))
    )
    (net (code "41") (name "PA0") (class "Default")
      (node (ref "P100") (pin "12") (pinfunction "12_12") (pintype "passive"))
      (node (ref "P102") (pin "12") (pinfunction "12_12") (pintype "passive"))
    )
    (net (code "42") (name "PA1") (class "Default")
      (node (ref "P100") (pin "14") (pinfunction "14_14") (pintype "passive"))
      (node (ref "P102") (pin "14") (pinfunction "14_14") (pintype "passive"))
    )
    (net (code "43") (name "PA2") (class "Default")
      (node (ref "P100") (pin "8") (pinfunction "8_8") (pintype "passive"))
      (node (ref "P102") (pin "8") (pinfunction "8_8") (pintype "passive"))
    )
    (net (code "44") (name "PA3") (class "Default")
      (node (ref "P100") (pin "10") (pinfunction "10_10") (pintype "passive"))
      (node (ref "P102") (pin "10") (pinfunction "10_10") (pintype "passive"))
    )
    (net (code "45") (name "PA4") (class "Default")
      (node (ref "P100") (pin "28") (pinfunction "28_28") (pintype "passive"))
      (node (ref "P102") (pin "28") (pinfunction "28_28") (pintype "passive"))
    )
    (net (code "46") (name "PA5") (class "Default")
      (node (ref "P100") (pin "26") (pinfunction "26_26") (pintype "passive"))
      (node (ref "P102") (pin "26") (pinfunction "26_26") (pintype "passive"))
    )
    (net (code "47") (name "PA6") (class "Default")
      (node (ref "P100") (pin "22") (pinfunction "22_22") (pintype "passive"))
      (node (ref "P102") (pin "22") (pinfunction "22_22") (pintype "passive"))
    )
    (net (code "48") (name "PA7") (class "Default")
      (node (ref "P100") (pin "20") (pinfunction "20_20") (pintype "passive"))
      (node (ref "P102") (pin "20") (pinfunction "20_20") (pintype "passive"))
    )
    (net (code "49") (name "PA9") (class "Default")
      (node (ref "P100") (pin "32") (pinfunction "32_32") (pintype "passive"))
      (node (ref "P102") (pin "32") (pinfunction "32_32") (pintype "passive"))
    )
    (net (code "50") (name "PA10") (class "Default")
      (node (ref "P100") (pin "16") (pinfunction "16_16") (pintype "passive"))
      (node (ref "P102") (pin "16") (pinfunction "16_16") (pintype "passive"))
    )
    (net (code "51") (name "PA15") (class "Default")
      (node (ref "P100") (pin "30") (pinfunction "30_30") (pintype "passive"))
      (node (ref "P102") (pin "30") (pinfunction "30_30") (pintype "passive"))
    )
    (net (code "52") (name "PB2") (class "Default")
      (node (ref "P100") (pin "6") (pinfunction "6_6") (pintype "passive"))
      (node (ref "P102") (pin "6") (pinfunction "6_6") (pintype "passive"))
      (node (ref "R517") (pin "2") (pinfunction "2_2") (pintype "bidirectional"))
      (node (ref "R518") (pin "1") (pinfunction "1_1") (pintype "bidirectional"))
    )
    (net (code "53") (name "PB10") (class "Default")
      (node (ref "D125") (pin "P$1") (pinfunction "1_P$1") (pintype "bidirectional"))
      (node (ref "D537") (pin "P$1") (pinfunction "1_P$1") (pintype "bidirectional"))
      (node (ref "EE_SCL") (pin "TP") (pinfunction "PP_TP") (pintype "input"))
      (node (ref "P100") (pin "54") (pinfunction "54_54") (pintype "passive"))
      (node (ref "P102") (pin "54") (pinfunction "54_54") (pintype "passive"))
      (node (ref "U105") (pin "P$6") (pinfunction "SCL_P$6") (pintype "input"))
      (node (ref "U500") (pin "3") (pinfunction "SCL_3") (pintype "bidirectional"))
      (node (ref "U520") (pin "5") (pinfunction "SCL_5") (pintype "bidirectional"))
    )
    (net (code "54") (name "PB11") (class "Default")
      (node (ref "D126") (pin "P$1") (pinfunction "1_P$1") (pintype "bidirectional"))
      (node (ref "D536") (pin "P$1") (pinfunction "1_P$1") (pintype "bidirectional"))
      (node (ref "EE_SDA") (pin "TP") (pinfunction "PP_TP") (pintype "input"))
      (node (ref "P100") (pin "52") (pinfunction "52_52") (pintype "passive"))
      (node (ref "P102") (pin "52") (pinfunction "52_52") (pintype "passive"))
      (node (ref "U105") (pin "P$5") (pinfunction "SDA_P$5") (pintype "bidirectional"))
      (node (ref "U500") (pin "4") (pinfunction "SDA_4") (pintype "bidirectional"))
      (node (ref "U520") (pin "6") (pinfunction "SDA_6") (pintype "bidirectional"))
    )
    (net (code "55") (name "PC0") (class "Default")
      (node (ref "P100") (pin "4") (pinfunction "4_4") (pintype "passive"))
      (node (ref "P102") (pin "4") (pinfunction "4_4") (pintype "passive"))
    )
    (net (code "56") (name "PC1") (class "Default")
      (node (ref "P100") (pin "2") (pinfunction "2_2") (pintype "passive"))
      (node (ref "P102") (pin "2") (pinfunction "2_2") (pintype "passive"))
    )
    (net (code "57") (name "PC3") (class "Default")
      (node (ref "P100") (pin "72") (pinfunction "72_72") (pintype "passive"))
      (node (ref "P102") (pin "72") (pinfunction "72_72") (pintype "passive"))
    )
    (net (code "58") (name "PC7") (class "Default")
      (node (ref "D532") (pin "P$1") (pinfunction "1_P$1") (pintype "bidirectional"))
      (node (ref "P100") (pin "23") (pinfunction "23_23") (pintype "passive"))
      (node (ref "P102") (pin "23") (pinfunction "23_23") (pintype "passive"))
      (node (ref "R531") (pin "2") (pinfunction "2_2") (pintype "bidirectional"))
      (node (ref "U520") (pin "7") (pinfunction "INT_7") (pintype "bidirectional"))
    )
    (net (code "59") (name "PC8") (class "Default")
      (node (ref "P100") (pin "18") (pinfunction "18_18") (pintype "passive"))
      (node (ref "P102") (pin "18") (pinfunction "18_18") (pintype "passive"))
    )
    (net (code "60") (name "PC9") (class "Default")
      (node (ref "P100") (pin "33") (pinfunction "33_33") (pintype "passive"))
      (node (ref "P102") (pin "33") (pinfunction "33_33") (pintype "passive"))
    )
    (net (code "61") (name "PC12") (class "Default")
      (node (ref "P100") (pin "74") (pinfunction "74_74") (pintype "passive"))
      (node (ref "P102") (pin "74") (pinfunction "74_74") (pintype "passive"))
    )
    (net (code "62") (name "PC14") (class "Default")
      (node (ref "P100") (pin "25") (pinfunction "25_25") (pintype "passive"))
      (node (ref "P102") (pin "25") (pinfunction "25_25") (pintype "passive"))
    )
    (net (code "63") (name "PC15") (class "Default")
      (node (ref "P100") (pin "27") (pinfunction "27_27") (pintype "passive"))
      (node (ref "P102") (pin "27") (pinfunction "27_27") (pintype "passive"))
    )
    (net (code "64") (name "PD6") (class "Default")
      (node (ref "P100") (pin "24") (pinfunction "24_24") (pintype "passive"))
      (node (ref "P102") (pin "24") (pinfunction "24_24") (pintype "passive"))
    )
    (net (code "65") (name "PD7") (class "Default")
      (node (ref "P100") (pin "31") (pinfunction "31_31") (pintype "passive"))
      (node (ref "P102") (pin "31") (pinfunction "31_31") (pintype "passive"))
    )
    (net (code "66") (name "PE7") (class "Default")
      (node (ref "P100") (pin "29") (pinfunction "29_29") (pintype "passive"))
      (node (ref "P102") (pin "29") (pinfunction "29_29") (pintype "passive"))
    )
    (net (code "67") (name "PG9") (class "Default")
      (node (ref "D124") (pin "P$1") (pinfunction "1_P$1") (pintype "bidirectional"))
      (node (ref "EE_WP") (pin "TP") (pinfunction "PP_TP") (pintype "input"))
      (node (ref "P100") (pin "76") (pinfunction "76_76") (pintype "passive"))
      (node (ref "P102") (pin "76") (pinfunction "76_76") (pintype "passive"))
      (node (ref "R108") (pin "2") (pinfunction "2_2") (pintype "bidirectional"))
      (node (ref "U105") (pin "P$7") (pinfunction "WP_P$7") (pintype "input"))
    )
    (net (code "68") (name "PG10") (class "Default")
      (node (ref "P100") (pin "78") (pinfunction "78_78") (pintype "passive"))
      (node (ref "P102") (pin "78") (pinfunction "78_78") (pintype "passive"))
      (node (ref "Q539") (pin "1") (pinfunction "G_1") (pintype "passive"))
      (node (ref "R540") (pin "1") (pinfunction "1_1") (pintype "bidirectional"))
    )
    (net (code "69") (name "PG12") (class "Default")
      (node (ref "P100") (pin "80") (pinfunction "80_80") (pintype "passive"))
      (node (ref "P102") (pin "80") (pinfunction "80_80") (pintype "passive"))
      (node (ref "U500") (pin "8") (pinfunction "ALRT_8") (pintype "bidirectional"))
    )
    (net (code "70") (name "PGND") (class "Default")
      (node (ref "C521") (pin "2") (pinfunction "2_2") (pintype "bidirectional"))
      (node (ref "C526") (pin "2") (pinfunction "2_2") (pintype "bidirectional"))
      (node (ref "C529") (pin "2") (pinfunction "2_2") (pintype "bidirectional"))
      (node (ref "C541") (pin "2") (pinfunction "2_2") (pintype "bidirectional"))
      (node (ref "C542") (pin "2") (pinfunction "2_2") (pintype "bidirectional"))
      (node (ref "E548") (pin "2") (pinfunction "2_2") (pintype "bidirectional"))
      (node (ref "U520") (pin "17") (pinfunction "PGND1_17") (pintype "bidirectional"))
      (node (ref "U520") (pin "18") (pinfunction "PGND2_18") (pintype "bidirectional"))
      (node (ref "U520") (pin "G1") (pinfunction "CTGND_G1") (pintype "bidirectional"))
    )
    (net (code "71") (name "PH0") (class "Default")
      (node (ref "P100") (pin "70") (pinfunction "70_70") (pintype "passive"))
      (node (ref "P102") (pin "70") (pinfunction "70_70") (pintype "passive"))
    )
    (net (code "72") (name "PMID") (class "Default")
      (node (ref "C529") (pin "1") (pinfunction "1_1") (pintype "bidirectional"))
      (node (ref "U520") (pin "23") (pinfunction "PMID_23") (pintype "bidirectional"))
    )
    (net (code "73") (name "PM_SW") (class "Default")
      (node (ref "C528") (pin "2") (pinfunction "2_2") (pintype "bidirectional"))
      (node (ref "L530") (pin "G1") (pinfunction "1_G1") (pintype "passive"))
      (node (ref "U520") (pin "19") (pinfunction "SW1_19") (pintype "bidirectional"))
      (node (ref "U520") (pin "20") (pinfunction "SW2_20") (pintype "bidirectional"))
    )
    (net (code "74") (name "PM_TS") (class "Default")
      (node (ref "R546") (pin "1") (pinfunction "1_1") (pintype "bidirectional"))
      (node (ref "R547") (pin "1") (pinfunction "1_1") (pintype "bidirectional"))
      (node (ref "U520") (pin "11") (pinfunction "TS_11") (pintype "bidirectional"))
    )
    (net (code "75") (name "POWERGOOD") (class "Default")
      (node (ref "Q121") (pin "1") (pinfunction "G_1") (pintype "passive"))
      (node (ref "U120") (pin "2") (pinfunction "/RST_2") (pintype "output"))
    )
    (net (code "76") (name "PSEL") (class "Default")
      (node (ref "R534") (pin "2") (pinfunction "2_2") (pintype "bidirectional"))
      (node (ref "U520") (pin "2") (pinfunction "PSEL_2") (pintype "bidirectional"))
    )
    (net (code "77") (name "TE") (class "Default")
      (node (ref "P100") (pin "35") (pinfunction "35_35") (pintype "passive"))
      (node (ref "P102") (pin "35") (pinfunction "35_35") (pintype "passive"))
    )
    (net (code "78") (name "THERM_PWR") (class "Default")
      (node (ref "R503") (pin "1") (pinfunction "1_1") (pintype "bidirectional"))
      (node (ref "U500") (pin "9") (pinfunction "THRM_9") (pintype "bidirectional"))
    )
    (net (code "79") (name "USB_DN") (class "Default")
      (node (ref "P100") (pin "77") (pinfunction "77_77") (pintype "passive"))
      (node (ref "P102") (pin "77") (pinfunction "77_77") (pintype "passive"))
    )
    (net (code "80") (name "USB_DP") (class "Default")
      (node (ref "P100") (pin "75") (pinfunction "75_75") (pintype "passive"))
      (node (ref "P102") (pin "75") (pinfunction "75_75") (pintype "passive"))
    )
    (net (code "81") (name "VBUS") (class "Default")
      (node (ref "C523") (pin "1") (pinfunction "1_1") (pintype "bidirectional"))
      (node (ref "C524") (pin "1") (pinfunction "1_1") (pintype "bidirectional"))
      (node (ref "C526") (pin "1") (pinfunction "1_1") (pintype "bidirectional"))
      (node (ref "D522") (pin "1") (pinfunction "1_1") (pintype "bidirectional"))
      (node (ref "P100") (pin "11") (pinfunction "11_11") (pintype "passive"))
      (node (ref "P102") (pin "11") (pinfunction "11_11") (pintype "passive"))
      (node (ref "R525") (pin "1") (pinfunction "1_1") (pintype "bidirectional"))
      (node (ref "U520") (pin "1") (pinfunction "VBUS_1") (pintype "bidirectional"))
    )
    (net (code "82") (name "VREGN") (class "Default")
      (node (ref "C527") (pin "1") (pinfunction "1_1") (pintype "bidirectional"))
      (node (ref "R534") (pin "1") (pinfunction "1_1") (pintype "bidirectional"))
      (node (ref "R538") (pin "1") (pinfunction "1_1") (pintype "bidirectional"))
      (node (ref "R546") (pin "2") (pinfunction "2_2") (pintype "bidirectional"))
      (node (ref "U520") (pin "22") (pinfunction "REGN_22") (pintype "bidirectional"))
    )
    (net (code "83") (name "VSYS") (class "Default")
      (node (ref "C541") (pin "1") (pinfunction "1_1") (pintype "bidirectional"))
      (node (ref "C542") (pin "1") (pinfunction "1_1") (pintype "bidirectional"))
      (node (ref "C544") (pin "1") (pinfunction "1_1") (pintype "bidirectional"))
      (node (ref "C545") (pin "1") (pinfunction "1_1") (pintype "bidirectional"))
      (node (ref "D543") (pin "P$2") (pinfunction "2_P$2") (pintype "bidirectional"))
      (node (ref "L530") (pin "G2") (pinfunction "2_G2") (pintype "passive"))
      (node (ref "P100") (pin "17") (pinfunction "17_17") (pintype "passive"))
      (node (ref "P102") (pin "17") (pinfunction "17_17") (pintype "passive"))
      (node (ref "U520") (pin "15") (pinfunction "SYS1_15") (pintype "bidirectional"))
      (node (ref "U520") (pin "16") (pinfunction "SYS2_16") (pintype "bidirectional"))
    )
    (net (code "84") (name "unconnected-(U520-NC-Pad24)") (class "Default")
      (node (ref "U520") (pin "24") (pinfunction "NC_24") (pintype "bidirectional"))
    )
    (net (code "85") (name "unconnected-(U520-PG_N-Pad3)") (class "Default")
      (node (ref "U520") (pin "3") (pinfunction "PG_N_3") (pintype "bidirectional"))
    )
    (net (code "86") (name "unconnected-(U520-QON_N-Pad12)") (class "Default")
      (node (ref "U520") (pin "12") (pinfunction "QON_N_12") (pintype "bidirectional"))
    )
    (net (code "87") (name "unconnected-(U520-STAT-Pad4)") (class "Default")
      (node (ref "U520") (pin "4") (pinfunction "STAT_4") (pintype "bidirectional"))
    )
  )
)
